# SDCARD.net
KiCad netlist of a schematic drawn in Altium Designer
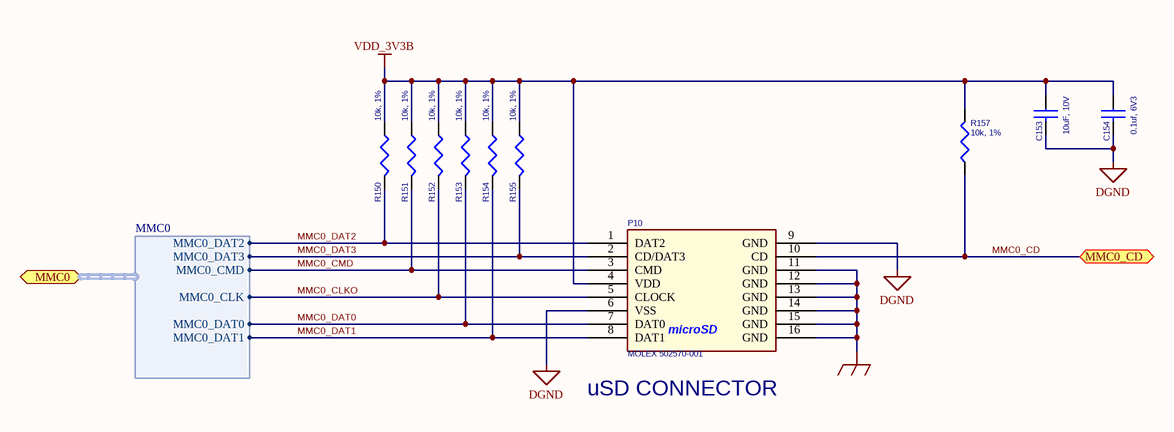
[diagram p0: SDCARD.SchDoc]

(export (version "E")
  (design (tool "Eeschema 10.0.6"))
  (components
    (comp (ref "C153")
      (value "10uF, 10V")
      (description "CAP CER 10UF 10V Y5V 0805")
      (fields
        (field (name "MANUFACTURER") "TDK Corporation")
        (field (name "MANUFACTURER PART NUMBER") "C2012Y5V1A106Z")
      )
      (libsource (lib "BEAGLEBONEBLACK_REV A5B") (part "CAP_10uF_Y5V_10V_10%_0805"))
    )
    (comp (ref "C154")
      (value "0.1uf, 6V3")
      (footprint "402")
      (description "CAP CER 0.1UF 6.3V 10% X5R 0402")
      (fields
        (field (name "MANUFACTURER") "TDK Corporation")
        (field (name "MANUFACTURER PART NUMBER") "C1005X5R0J104K050BA")
      )
      (libsource (lib "BEAGLEBONEBLACK_REV A5B") (part "CAP_0.1uF_X7R_16V_10% 0402"))
    )
    (comp (ref "P10")
      (value "MOLEX 502570-001")
      (footprint "SD-MICRO-SCHA5B0300")
      (description "CONN MICRO SD R/A PUSH-PUSH SMD")
      (fields
        (field (name "MANUFACTURER") "Molex Inc")
        (field (name "MANUFACTURER PART NUMBER") "5025700893")
      )
      (libsource (lib "BEAGLEBONEBLACK_REV A5B") (part "microSD_CONN_2"))
    )
    (comp (ref "R150")
      (value "10k, 1%")
      (footprint "402")
      (description "RES 10K OHM 1/16W 5% 0402 SMD")
      (fields
        (field (name "MANUFACTURER") "Rohm Semiconductor")
        (field (name "MANUFACTURER PART NUMBER") "MCR01MZPJ103")
      )
      (libsource (lib "BEAGLEBONEBLACK_REV A5B") (part "RES_10K_1/16W_1%_0402"))
    )
    (comp (ref "R151")
      (value "10k, 1%")
      (footprint "402")
      (description "RES 10K OHM 1/16W 5% 0402 SMD")
      (fields
        (field (name "MANUFACTURER") "Rohm Semiconductor")
        (field (name "MANUFACTURER PART NUMBER") "MCR01MZPJ103")
      )
      (libsource (lib "BEAGLEBONEBLACK_REV A5B") (part "RES_10K_1/16W_1%_0402"))
    )
    (comp (ref "R152")
      (value "10k, 1%")
      (footprint "402")
      (description "RES 10K OHM 1/16W 5% 0402 SMD")
      (fields
        (field (name "MANUFACTURER") "Rohm Semiconductor")
        (field (name "MANUFACTURER PART NUMBER") "MCR01MZPJ103")
      )
      (libsource (lib "BEAGLEBONEBLACK_REV A5B") (part "RES_10K_1/16W_1%_0402"))
    )
    (comp (ref "R153")
      (value "10k, 1%")
      (footprint "402")
      (description "RES 10K OHM 1/16W 5% 0402 SMD")
      (fields
        (field (name "MANUFACTURER") "Rohm Semiconductor")
        (field (name "MANUFACTURER PART NUMBER") "MCR01MZPJ103")
      )
      (libsource (lib "BEAGLEBONEBLACK_REV A5B") (part "RES_10K_1/16W_1%_0402"))
    )
    (comp (ref "R154")
      (value "10k, 1%")
      (footprint "402")
      (description "RES 10K OHM 1/16W 5% 0402 SMD")
      (fields
        (field (name "MANUFACTURER") "Rohm Semiconductor")
        (field (name "MANUFACTURER PART NUMBER") "MCR01MZPJ103")
      )
      (libsource (lib "BEAGLEBONEBLACK_REV A5B") (part "RES_10K_1/16W_1%_0402"))
    )
    (comp (ref "R155")
      (value "10k, 1%")
      (footprint "402")
      (description "RES 10K OHM 1/16W 5% 0402 SMD")
      (fields
        (field (name "MANUFACTURER") "Rohm Semiconductor")
        (field (name "MANUFACTURER PART NUMBER") "MCR01MZPJ103")
      )
      (libsource (lib "BEAGLEBONEBLACK_REV A5B") (part "RES_10K_1/16W_1%_0402"))
    )
    (comp (ref "R157")
      (value "10k, 1%")
      (footprint "402")
      (description "RES 10K OHM 1/16W 5% 0402 SMD")
      (fields
        (field (name "MANUFACTURER") "Rohm Semiconductor")
        (field (name "MANUFACTURER PART NUMBER") "MCR01MZPJ103")
      )
      (libsource (lib "BEAGLEBONEBLACK_REV A5B") (part "RES_10K_1/16W_1%_0402"))
    )
  )
  (nets
    (net (code "2") (name "/MMC0_CD") (class "Default")
      (node (ref "P10") (pin "10") (pinfunction "CD_10") (pintype "passive"))
      (node (ref "R157") (pin "1") (pinfunction "1_1") (pintype "passive"))
    )
    (net (code "3") (name "/MMC0_CLKO") (class "Default")
      (node (ref "P10") (pin "5") (pinfunction "CLOCK_5") (pintype "passive"))
      (node (ref "R152") (pin "2") (pinfunction "2_2") (pintype "passive"))
    )
    (net (code "4") (name "/MMC0_CMD") (class "Default")
      (node (ref "P10") (pin "3") (pinfunction "CMD_3") (pintype "passive"))
      (node (ref "R151") (pin "2") (pinfunction "2_2") (pintype "passive"))
    )
    (net (code "5") (name "/MMC0_DAT0") (class "Default")
      (node (ref "P10") (pin "7") (pinfunction "DAT0_7") (pintype "passive"))
      (node (ref "R153") (pin "2") (pinfunction "2_2") (pintype "passive"))
    )
    (net (code "6") (name "/MMC0_DAT1") (class "Default")
      (node (ref "P10") (pin "8") (pinfunction "DAT1_8") (pintype "passive"))
      (node (ref "R154") (pin "2") (pinfunction "2_2") (pintype "passive"))
    )
    (net (code "7") (name "/MMC0_DAT2") (class "Default")
      (node (ref "P10") (pin "1") (pinfunction "DAT2_1") (pintype "passive"))
      (node (ref "R150") (pin "2") (pinfunction "2_2") (pintype "passive"))
    )
    (net (code "8") (name "/MMC0_DAT3") (class "Default")
      (node (ref "P10") (pin "2") (pinfunction "CD/DAT3_2") (pintype "passive"))
      (node (ref "R155") (pin "2") (pinfunction "2_2") (pintype "passive"))
    )
    (net (code "10") (name "DGND") (class "Default")
      (node (ref "C153") (pin "2") (pinfunction "2_2") (pintype "passive"))
      (node (ref "C154") (pin "2") (pinfunction "2_2") (pintype "passive"))
      (node (ref "P10") (pin "6") (pinfunction "VSS_6") (pintype "power_in"))
      (node (ref "P10") (pin "9") (pinfunction "GND_9") (pintype "power_in"))
    )
    (net (code "11") (name "GND_EARTH") (class "Default")
      (node (ref "P10") (pin "11") (pinfunction "GND_11") (pintype "power_in"))
      (node (ref "P10") (pin "12") (pinfunction "GND_12") (pintype "power_in"))
      (node (ref "P10") (pin "13") (pinfunction "GND_13") (pintype "passive"))
      (node (ref "P10") (pin "14") (pinfunction "GND_14") (pintype "passive"))
      (node (ref "P10") (pin "15") (pinfunction "GND_15") (pintype "passive"))
      (node (ref "P10") (pin "16") (pinfunction "GND_16") (pintype "passive"))
    )
    (net (code "12") (name "VDD_3V3B") (class "Default")
      (node (ref "C153") (pin "1") (pinfunction "1_1") (pintype "passive"))
      (node (ref "C154") (pin "1") (pinfunction "1_1") (pintype "passive"))
      (node (ref "P10") (pin "4") (pinfunction "VDD_4") (pintype "power_in"))
      (node (ref "R150") (pin "1") (pinfunction "1_1") (pintype "passive"))
      (node (ref "R151") (pin "1") (pinfunction "1_1") (pintype "passive"))
      (node (ref "R152") (pin "1") (pinfunction "1_1") (pintype "passive"))
      (node (ref "R153") (pin "1") (pinfunction "1_1") (pintype "passive"))
      (node (ref "R154") (pin "1") (pinfunction "1_1") (pintype "passive"))
      (node (ref "R155") (pin "1") (pinfunction "1_1") (pintype "passive"))
      (node (ref "R157") (pin "2") (pinfunction "2_2") (pintype "passive"))
    )
  )
)
